# power.net
KiCad netlist of a schematic drawn in Altium Designer
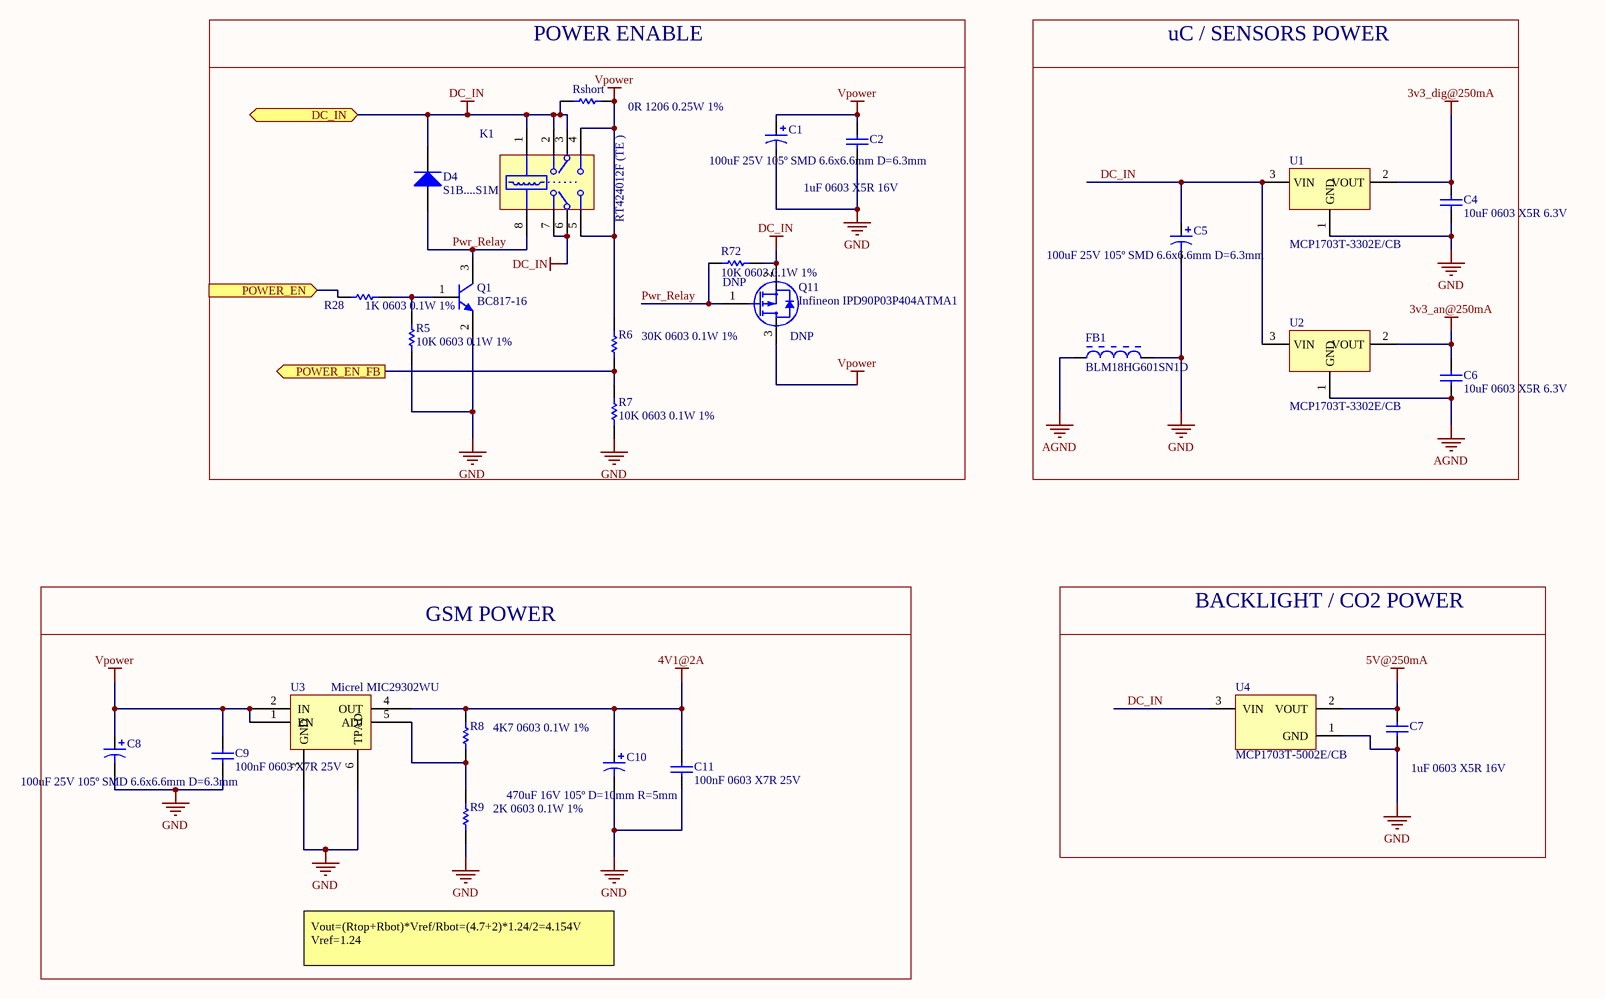
[diagram p0: power.SchDoc]

(export (version "E")
  (design (tool "Eeschema 10.0.6"))
  (components
    (comp (ref "C1")
      (value "100uF 25V 105º SMD 6.6x6.6mm D=6.3mm")
      (footprint "PCB-5eg0a5nygcrzw5ibm1j9-1")
      (fields (field (name "MANUFACTURER PART NUMBER") "VZL101M1ETR-0607") (field (name "TOLERANCE") "20%"))
      (libsource (lib "CommunityVault") (part "CMP-a6d16ad512617916-1"))
    )
    (comp (ref "C2")
      (value "1uF 0603 X5R 16V")
      (footprint "CAPC1608X60X35NL10T15")
      (fields (field (name "MANUFACTURER PART NUMBER") "GRM185R61C105KE44D"))
      (libsource (lib "CommunityVault") (part "CMP-119984-2"))
    )
    (comp (ref "C4")
      (value "10uF 0603 X5R 6.3V")
      (footprint "CAPC1608X60X35NL10T15")
      (libsource (lib "CommunityVault") (part "CMP-121364-8"))
    )
    (comp (ref "C5")
      (value "100uF 25V 105º SMD 6.6x6.6mm D=6.3mm")
      (footprint "PCB-5eg0a5nygcrzw5ibm1j9-1")
      (fields (field (name "MANUFACTURER PART NUMBER") "VZL101M1ETR-0607") (field (name "TOLERANCE") "20%"))
      (libsource (lib "CommunityVault") (part "CMP-a6d16ad512617916-1"))
    )
    (comp (ref "C6")
      (value "10uF 0603 X5R 6.3V")
      (footprint "CAPC1608X60X35NL10T15")
      (libsource (lib "CommunityVault") (part "CMP-121364-8"))
    )
    (comp (ref "C7")
      (value "1uF 0603 X5R 16V")
      (footprint "CAPC1608X60X35NL10T15")
      (fields (field (name "MANUFACTURER PART NUMBER") "GRM185R61C105KE44D"))
      (libsource (lib "CommunityVault") (part "CMP-119984-2"))
    )
    (comp (ref "C8")
      (value "100uF 25V 105º SMD 6.6x6.6mm D=6.3mm")
      (footprint "PCB-5eg0a5nygcrzw5ibm1j9-1")
      (fields (field (name "MANUFACTURER PART NUMBER") "VZL101M1ETR-0607") (field (name "TOLERANCE") "20%"))
      (libsource (lib "CommunityVault") (part "CMP-a6d16ad512617916-1"))
    )
    (comp (ref "C9")
      (value "100nF 0603 X7R 25V")
      (footprint "CAPC1608X60X35NL10T15")
      (libsource (lib "CommunityVault") (part "CMP-c41a0d2b65641bdd-3"))
    )
    (comp (ref "C10")
      (value "470uF 16V 105º D=10mm R=5mm")
      (footprint "PCBComponent_1 - duplicate")
      (fields (field (name "MANUFACTURER PART NUMBER") "477CKH016M"))
      (libsource (lib "CommunityVault") (part "CMP-ebd022d405293417-3"))
    )
    (comp (ref "C11")
      (value "100nF 0603 X7R 25V")
      (footprint "CAPC1608X60X35NL10T15")
      (libsource (lib "CommunityVault") (part "CMP-c41a0d2b65641bdd-3"))
    )
    (comp (ref "D4")
      (value "S1B....S1M (DO-214)")
      (footprint "PCB-niliznqw36k7etm1u9na-1")
      (fields (field (name "MANUFACTURER PART NUMBER") "S1BB-13-F"))
      (libsource (lib "CommunityVault") (part "CMP-50d799d860158f10-1"))
    )
    (comp (ref "FB1")
      (value "BLM18HG601SN1D")
      (footprint "MURA-BLM18-F-H1-CHIP-2_V")
      (libsource (lib "CommunityVault") (part "CMP-19299602-3"))
    )
    (comp (ref "K1")
      (value "SYM-d1a918a3c97c0e6e-1")
      (footprint "PCB-gjrzw9dtiyu3qrueb5gw-1")
      (description "Relay; E-Mech; Gen Purp; DPDT; Cur-Rtg 8A; Ctrl-V 12DC; Vol-Rtg 277/30AC/DC; PCB Mnt")
      (fields (field (name "MANUFACTURER PART NUMBER") "RT424012F (TE )"))
      (libsource (lib "CommunityVault") (part "CMP-48a583f3a11c9762-9"))
    )
    (comp (ref "Q1")
      (value "BC817-16")
      (footprint "PCB-856332-1")
      (description "TRANS NPN 45V 500mA SMD SOT23-3")
      (libsource (lib "CommunityVault") (part "CMP-856332-3"))
    )
    (comp (ref "Q11")
      (value "Infineon IPD90P03P404ATMA1")
      (footprint "DPAK IPD90P03P404ATMA1")
      (description "Single P-Channel 30 V 4.5 mOhm 100 nC OptiMOS Power Mosfet - TO-252-3-11")
      (fields (field (name "MANUFACTURER PART NUMBER") "IPD90P03P404ATMA1") (field (name "DNP") "DNP"))
      (libsource (lib "CommunityVault") (part "CMP-3103264-4"))
    )
    (comp (ref "R5")
      (value "10K 0603 0.1W 1%")
      (footprint "RESC1609X55X30ML10T20")
      (fields (field (name "TOLERANCE") "1%"))
      (libsource (lib "CommunityVault") (part "CMP-4716590-9"))
    )
    (comp (ref "R6")
      (value "30K 0603 0.1W 1%")
      (footprint "RESC1609X55X30ML10T20")
      (fields (field (name "TOLERANCE") "1%"))
      (libsource (lib "CommunityVault") (part "CMP-3655986-6"))
    )
    (comp (ref "R7")
      (value "10K 0603 0.1W 1%")
      (footprint "RESC1609X55X30ML10T20")
      (fields (field (name "TOLERANCE") "1%"))
      (libsource (lib "CommunityVault") (part "CMP-4716590-9"))
    )
    (comp (ref "R8")
      (value "4K7 0603 0.1W 1%")
      (footprint "RESC1609X55X30ML10T20")
      (fields (field (name "TOLERANCE") "1%"))
      (libsource (lib "CommunityVault") (part "CMP-3655986-6"))
    )
    (comp (ref "R9")
      (value "2K 0603 0.1W 1%")
      (footprint "RESC1609X55X30ML10T20")
      (fields (field (name "TOLERANCE") "1%"))
      (libsource (lib "CommunityVault") (part "CMP-3655986-6"))
    )
    (comp (ref "R28")
      (value "1K 0603 0.1W 1%")
      (footprint "RESC1609X55X30ML10T20")
      (fields (field (name "MANUFACTURER PART NUMBER") "CR0603-FX-1001ELF"))
      (libsource (lib "CommunityVault") (part "CMP-a61f6f36030f79d8-4"))
    )
    (comp (ref "R72")
      (value "10K 0603 0.1W 1%")
      (footprint "RESC1609X55X30ML10T20")
      (fields (field (name "TOLERANCE") "1%") (field (name "DNP") "DNP"))
      (libsource (lib "CommunityVault") (part "CMP-4716590-9"))
    )
    (comp (ref "Rshort")
      (value "0R 1206 0.25W 1%")
      (footprint "PCB-sxvxwfnl72ysl1kmtzgv-1")
      (fields (field (name "MANUFACTURER PART NUMBER") "RC1206JR-070RL"))
      (libsource (lib "CommunityVault") (part "CMP-3f1bf473a47ce0dc-5"))
    )
    (comp (ref "U1")
      (value "MCP1703T-3302E/CB")
      (footprint "SOT-23A-CB3_L")
      (libsource (lib "CommunityVault") (part "CMP-1493313-4"))
    )
    (comp (ref "U2")
      (value "MCP1703T-3302E/CB")
      (footprint "SOT-23A-CB3_L")
      (libsource (lib "CommunityVault") (part "CMP-1493313-4"))
    )
    (comp (ref "U3")
      (value "Micrel MIC29302WU")
      (footprint "TI-KTT5_N")
      (description "MIC29302 Series 3 A 1.24 to 26 V ADJ Output Voltage LDO Regulator - TO-263-5")
      (libsource (lib "CommunityVault") (part "SYM--116"))
    )
    (comp (ref "U4")
      (value "MCP1703T-5002E/CB")
      (footprint "SOT-23A-CB3_L")
      (libsource (lib "CommunityVault") (part "PM-LINEREG-MCP1703-IL3A"))
    )
  )
  (nets
    (net (code "1") (name "/POWER_EN") (class "Default")
      (node (ref "R28") (pin "1") (pinfunction "1_1") (pintype "passive"))
    )
    (net (code "2") (name "/POWER_EN_FB") (class "Default")
      (node (ref "R6") (pin "1") (pinfunction "1_1") (pintype "passive"))
      (node (ref "R7") (pin "1") (pinfunction "1_1") (pintype "passive"))
    )
    (net (code "3") (name "/Pwr_Relay") (class "Default")
      (node (ref "D4") (pin "1") (pinfunction "A_1") (pintype "passive"))
      (node (ref "K1") (pin "8") (pinfunction "8_8") (pintype "passive"))
      (node (ref "Q1") (pin "3") (pinfunction "C_3") (pintype "passive"))
      (node (ref "Q11") (pin "1") (pinfunction "G_1") (pintype "passive"))
      (node (ref "R72") (pin "1") (pinfunction "1_1") (pintype "passive"))
    )
    (net (code "4") (name "3v3_an@250mA") (class "Default")
      (node (ref "C6") (pin "2") (pinfunction "2_2") (pintype "passive"))
      (node (ref "U2") (pin "2") (pinfunction "VOUT_2") (pintype "power_in"))
    )
    (net (code "5") (name "3v3_dig@250mA") (class "Default")
      (node (ref "C4") (pin "2") (pinfunction "2_2") (pintype "passive"))
      (node (ref "U1") (pin "2") (pinfunction "VOUT_2") (pintype "power_in"))
    )
    (net (code "6") (name "4V1@2A") (class "Default")
      (node (ref "C10") (pin "1") (pinfunction "1_1") (pintype "passive"))
      (node (ref "C11") (pin "2") (pinfunction "2_2") (pintype "passive"))
      (node (ref "R8") (pin "2") (pinfunction "2_2") (pintype "passive"))
      (node (ref "U3") (pin "4") (pinfunction "OUT_4") (pintype "passive"))
    )
    (net (code "7") (name "5V@250mA") (class "Default")
      (node (ref "C7") (pin "1") (pinfunction "1_1") (pintype "passive"))
      (node (ref "U4") (pin "2") (pinfunction "VOUT_2") (pintype "power_in"))
    )
    (net (code "8") (name "AGND") (class "Default")
      (node (ref "C6") (pin "1") (pinfunction "1_1") (pintype "passive"))
      (node (ref "FB1") (pin "1") (pinfunction "1_1") (pintype "passive"))
      (node (ref "U2") (pin "1") (pinfunction "GND_1") (pintype "power_in"))
    )
    (net (code "9") (name "DC_IN") (class "Default")
      (node (ref "C5") (pin "1") (pinfunction "1_1") (pintype "passive"))
      (node (ref "D4") (pin "2") (pinfunction "K_2") (pintype "passive"))
      (node (ref "K1") (pin "1") (pinfunction "1_1") (pintype "passive"))
      (node (ref "K1") (pin "2") (pinfunction "2_2") (pintype "passive"))
      (node (ref "K1") (pin "3") (pinfunction "3_3") (pintype "passive"))
      (node (ref "K1") (pin "6") (pinfunction "6_6") (pintype "passive"))
      (node (ref "K1") (pin "7") (pinfunction "7_7") (pintype "passive"))
      (node (ref "Q11") (pin "2") (pinfunction "S_2") (pintype "passive"))
      (node (ref "R72") (pin "2") (pinfunction "2_2") (pintype "passive"))
      (node (ref "Rshort") (pin "1") (pinfunction "1_1") (pintype "passive"))
      (node (ref "U1") (pin "3") (pinfunction "VIN_3") (pintype "power_in"))
      (node (ref "U2") (pin "3") (pinfunction "VIN_3") (pintype "power_in"))
      (node (ref "U4") (pin "3") (pinfunction "VIN_3") (pintype "power_in"))
    )
    (net (code "10") (name "GND") (class "Default")
      (node (ref "C1") (pin "2") (pinfunction "2_2") (pintype "passive"))
      (node (ref "C10") (pin "2") (pinfunction "2_2") (pintype "passive"))
      (node (ref "C11") (pin "1") (pinfunction "1_1") (pintype "passive"))
      (node (ref "C2") (pin "2") (pinfunction "2_2") (pintype "passive"))
      (node (ref "C4") (pin "1") (pinfunction "1_1") (pintype "passive"))
      (node (ref "C5") (pin "2") (pinfunction "2_2") (pintype "passive"))
      (node (ref "C7") (pin "2") (pinfunction "2_2") (pintype "passive"))
      (node (ref "C8") (pin "2") (pinfunction "2_2") (pintype "passive"))
      (node (ref "C9") (pin "1") (pinfunction "1_1") (pintype "passive"))
      (node (ref "FB1") (pin "2") (pinfunction "2_2") (pintype "passive"))
      (node (ref "Q1") (pin "2") (pinfunction "E_2") (pintype "passive"))
      (node (ref "R5") (pin "2") (pinfunction "2_2") (pintype "passive"))
      (node (ref "R7") (pin "2") (pinfunction "2_2") (pintype "passive"))
      (node (ref "R9") (pin "1") (pinfunction "1_1") (pintype "passive"))
      (node (ref "U1") (pin "1") (pinfunction "GND_1") (pintype "power_in"))
      (node (ref "U3") (pin "3") (pinfunction "GND_3") (pintype "passive"))
      (node (ref "U3") (pin "6") (pinfunction "TPAD_6") (pintype "passive"))
      (node (ref "U4") (pin "1") (pinfunction "GND_1") (pintype "power_in"))
    )
    (net (code "11") (name "Net-(Q1-B)") (class "Default")
      (node (ref "Q1") (pin "1") (pinfunction "B_1") (pintype "passive"))
      (node (ref "R28") (pin "2") (pinfunction "2_2") (pintype "passive"))
      (node (ref "R5") (pin "1") (pinfunction "1_1") (pintype "passive"))
    )
    (net (code "12") (name "Net-(U3-ADJ)") (class "Default")
      (node (ref "R8") (pin "1") (pinfunction "1_1") (pintype "passive"))
      (node (ref "R9") (pin "2") (pinfunction "2_2") (pintype "passive"))
      (node (ref "U3") (pin "5") (pinfunction "ADJ_5") (pintype "passive"))
    )
    (net (code "13") (name "Vpower") (class "Default")
      (node (ref "C1") (pin "1") (pinfunction "1_1") (pintype "passive"))
      (node (ref "C2") (pin "1") (pinfunction "1_1") (pintype "passive"))
      (node (ref "C8") (pin "1") (pinfunction "1_1") (pintype "passive"))
      (node (ref "C9") (pin "2") (pinfunction "2_2") (pintype "passive"))
      (node (ref "K1") (pin "4") (pinfunction "4_4") (pintype "passive"))
      (node (ref "K1") (pin "5") (pinfunction "5_5") (pintype "passive"))
      (node (ref "Q11") (pin "3") (pinfunction "D_3") (pintype "passive"))
      (node (ref "R6") (pin "2") (pinfunction "2_2") (pintype "passive"))
      (node (ref "Rshort") (pin "2") (pinfunction "2_2") (pintype "passive"))
      (node (ref "U3") (pin "1") (pinfunction "EN_1") (pintype "passive"))
      (node (ref "U3") (pin "2") (pinfunction "IN_2") (pintype "passive"))
    )
  )
)
